# Warmie_Helper_Board.net
KiCad netlist of a schematic drawn in EAGLE
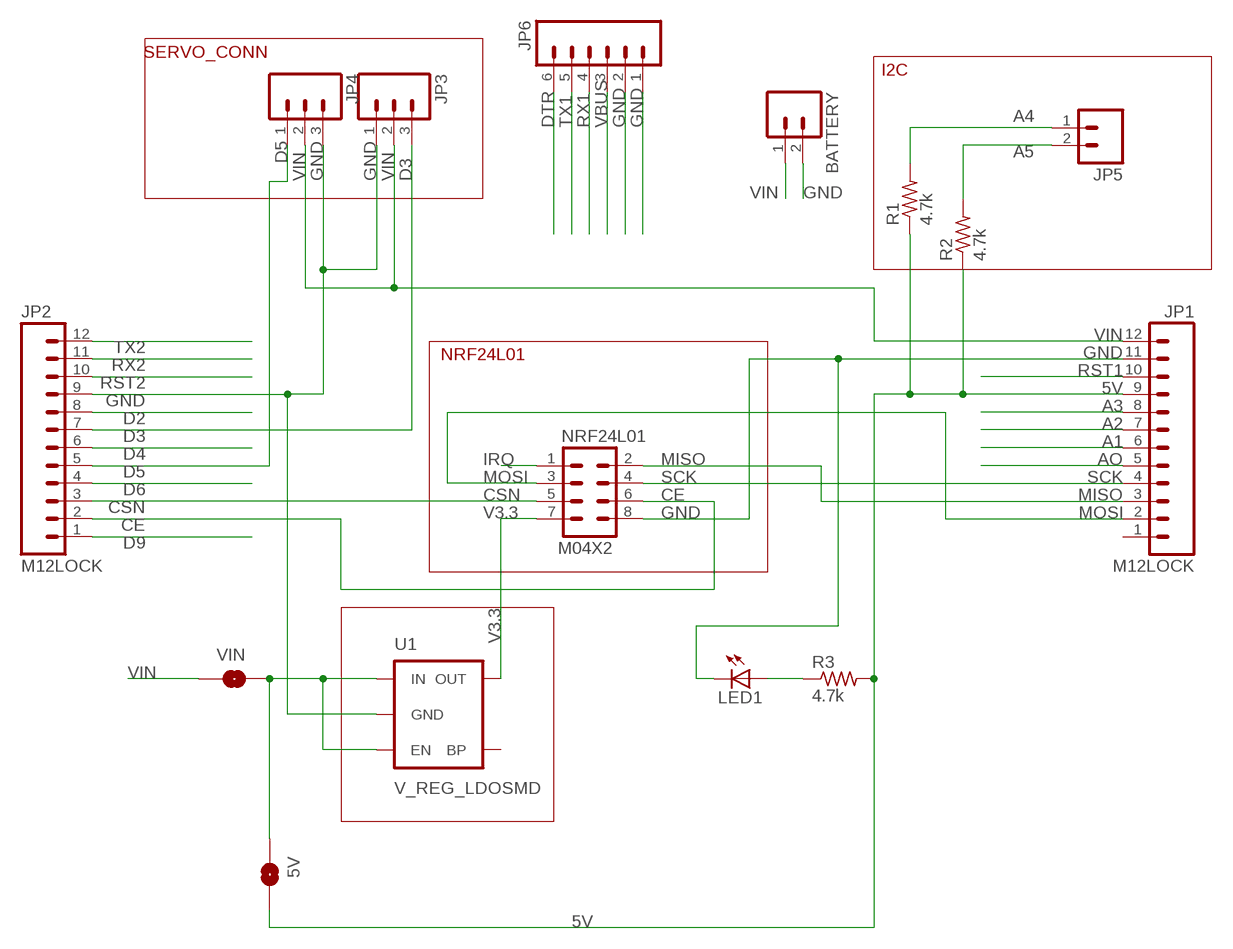
[diagram p0: schematic, sheet 1]

(export (version "E")
  (design (tool "Eeschema 10.0.6"))
  (components
    (comp (ref "5V")
      (value "SOLDERJUMPERNO")
      (footprint "eagle-import:SJ_2S-NO")
      (libsource (lib "eagle-import") (part "SOLDERJUMPERNO"))
    )
    (comp (ref "BATTERY")
      (value "M02LOCK")
      (footprint "eagle-import:1X02_LOCK")
      (libsource (lib "eagle-import") (part "M02LOCK"))
    )
    (comp (ref "JP1")
      (value "M12LOCK")
      (footprint "eagle-import:1X12_LOCK")
      (libsource (lib "eagle-import") (part "M12LOCK"))
    )
    (comp (ref "JP2")
      (value "M12LOCK")
      (footprint "eagle-import:1X12_LOCK")
      (libsource (lib "eagle-import") (part "M12LOCK"))
    )
    (comp (ref "JP3")
      (value "M03LOCK")
      (footprint "eagle-import:1X03_LOCK")
      (libsource (lib "eagle-import") (part "M03LOCK"))
    )
    (comp (ref "JP4")
      (value "M03LOCK")
      (footprint "eagle-import:1X03_LOCK")
      (libsource (lib "eagle-import") (part "M03LOCK"))
    )
    (comp (ref "JP5")
      (value "M02LOCK")
      (footprint "eagle-import:1X02_LOCK")
      (libsource (lib "eagle-import") (part "M02LOCK"))
    )
    (comp (ref "JP6")
      (value "M06LOCK")
      (footprint "eagle-import:1X06_LOCK")
      (libsource (lib "eagle-import") (part "M06LOCK"))
    )
    (comp (ref "LED1")
      (value "LEDSML0603")
      (footprint "eagle-import:SML0603")
      (libsource (lib "eagle-import") (part "LEDSML0603"))
    )
    (comp (ref "NRF24L01")
      (value "M04X2")
      (footprint "eagle-import:2X4")
      (libsource (lib "eagle-import") (part "M04X2"))
    )
    (comp (ref "R1")
      (value "4.7k")
      (footprint "eagle-import:M0805")
      (libsource (lib "eagle-import") (part "R-US_M0805"))
    )
    (comp (ref "R2")
      (value "4.7k")
      (footprint "eagle-import:M0805")
      (libsource (lib "eagle-import") (part "R-US_M0805"))
    )
    (comp (ref "R3")
      (value "4.7k")
      (footprint "eagle-import:M0805")
      (libsource (lib "eagle-import") (part "R-US_M0805"))
    )
    (comp (ref "U1")
      (value "V_REG_LDOSMD")
      (footprint "eagle-import:SOT23-5")
      (libsource (lib "eagle-import") (part "V_REG_LDOSMD"))
    )
    (comp (ref "VIN")
      (value "SOLDERJUMPERNO")
      (footprint "eagle-import:SJ_2S-NO")
      (libsource (lib "eagle-import") (part "SOLDERJUMPERNO"))
    )
  )
  (nets
    (net (code "1") (name "/5V") (class "Default")
      (node (ref "5V") (pin "2") (pinfunction "2_2") (pintype "passive"))
      (node (ref "JP1") (pin "9") (pinfunction "9_9") (pintype "passive"))
      (node (ref "R1") (pin "1") (pinfunction "1_1") (pintype "passive"))
      (node (ref "R2") (pin "1") (pinfunction "1_1") (pintype "passive"))
      (node (ref "R3") (pin "2") (pinfunction "2_2") (pintype "passive"))
    )
    (net (code "2") (name "/A1") (class "Default")
      (node (ref "JP1") (pin "6") (pinfunction "6_6") (pintype "passive"))
    )
    (net (code "3") (name "/A2") (class "Default")
      (node (ref "JP1") (pin "7") (pinfunction "7_7") (pintype "passive"))
    )
    (net (code "4") (name "/A3") (class "Default")
      (node (ref "JP1") (pin "8") (pinfunction "8_8") (pintype "passive"))
    )
    (net (code "5") (name "/A4") (class "Default")
      (node (ref "JP5") (pin "1") (pinfunction "1_1") (pintype "passive"))
      (node (ref "R1") (pin "2") (pinfunction "2_2") (pintype "passive"))
    )
    (net (code "6") (name "/A5") (class "Default")
      (node (ref "JP5") (pin "2") (pinfunction "2_2") (pintype "passive"))
      (node (ref "R2") (pin "2") (pinfunction "2_2") (pintype "passive"))
    )
    (net (code "7") (name "/AO") (class "Default")
      (node (ref "JP1") (pin "5") (pinfunction "5_5") (pintype "passive"))
    )
    (net (code "8") (name "/CE") (class "Default")
      (node (ref "JP2") (pin "2") (pinfunction "2_2") (pintype "passive"))
      (node (ref "NRF24L01") (pin "6") (pinfunction "6_6") (pintype "passive"))
    )
    (net (code "9") (name "/CSN") (class "Default")
      (node (ref "JP2") (pin "3") (pinfunction "3_3") (pintype "passive"))
      (node (ref "NRF24L01") (pin "5") (pinfunction "5_5") (pintype "passive"))
    )
    (net (code "10") (name "/D2") (class "Default")
      (node (ref "JP2") (pin "8") (pinfunction "8_8") (pintype "passive"))
    )
    (net (code "11") (name "/D3") (class "Default")
      (node (ref "JP2") (pin "7") (pinfunction "7_7") (pintype "passive"))
      (node (ref "JP3") (pin "3") (pinfunction "3_3") (pintype "passive"))
    )
    (net (code "12") (name "/D4") (class "Default")
      (node (ref "JP2") (pin "6") (pinfunction "6_6") (pintype "passive"))
    )
    (net (code "13") (name "/D5") (class "Default")
      (node (ref "JP2") (pin "5") (pinfunction "5_5") (pintype "passive"))
      (node (ref "JP4") (pin "1") (pinfunction "1_1") (pintype "passive"))
    )
    (net (code "14") (name "/D6") (class "Default")
      (node (ref "JP2") (pin "4") (pinfunction "4_4") (pintype "passive"))
    )
    (net (code "15") (name "/D9") (class "Default")
      (node (ref "JP2") (pin "1") (pinfunction "1_1") (pintype "passive"))
    )
    (net (code "16") (name "/DTR") (class "Default")
      (node (ref "JP6") (pin "6") (pinfunction "6_6") (pintype "passive"))
    )
    (net (code "17") (name "/GND") (class "Default")
      (node (ref "BATTERY") (pin "2") (pinfunction "2_2") (pintype "passive"))
      (node (ref "JP1") (pin "11") (pinfunction "11_11") (pintype "passive"))
      (node (ref "JP2") (pin "9") (pinfunction "9_9") (pintype "passive"))
      (node (ref "JP3") (pin "1") (pinfunction "1_1") (pintype "passive"))
      (node (ref "JP4") (pin "3") (pinfunction "3_3") (pintype "passive"))
      (node (ref "JP6") (pin "1") (pinfunction "1_1") (pintype "passive"))
      (node (ref "JP6") (pin "2") (pinfunction "2_2") (pintype "passive"))
      (node (ref "LED1") (pin "C") (pinfunction "C_C") (pintype "passive"))
      (node (ref "NRF24L01") (pin "8") (pinfunction "8_8") (pintype "passive"))
      (node (ref "U1") (pin "2") (pinfunction "GND_2") (pintype "input"))
    )
    (net (code "18") (name "/IRQ") (class "Default")
      (node (ref "NRF24L01") (pin "1") (pinfunction "1_1") (pintype "passive"))
    )
    (net (code "19") (name "/MISO") (class "Default")
      (node (ref "JP1") (pin "3") (pinfunction "3_3") (pintype "passive"))
      (node (ref "NRF24L01") (pin "2") (pinfunction "2_2") (pintype "passive"))
    )
    (net (code "20") (name "/MOSI") (class "Default")
      (node (ref "JP1") (pin "2") (pinfunction "2_2") (pintype "passive"))
      (node (ref "NRF24L01") (pin "3") (pinfunction "3_3") (pintype "passive"))
    )
    (net (code "21") (name "/RST1") (class "Default")
      (node (ref "JP1") (pin "10") (pinfunction "10_10") (pintype "passive"))
    )
    (net (code "22") (name "/RST2") (class "Default")
      (node (ref "JP2") (pin "10") (pinfunction "10_10") (pintype "passive"))
    )
    (net (code "23") (name "/RX1") (class "Default")
      (node (ref "JP6") (pin "4") (pinfunction "4_4") (pintype "passive"))
    )
    (net (code "24") (name "/RX2") (class "Default")
      (node (ref "JP2") (pin "11") (pinfunction "11_11") (pintype "passive"))
    )
    (net (code "25") (name "/SCK") (class "Default")
      (node (ref "JP1") (pin "4") (pinfunction "4_4") (pintype "passive"))
      (node (ref "NRF24L01") (pin "4") (pinfunction "4_4") (pintype "passive"))
    )
    (net (code "26") (name "/TX1") (class "Default")
      (node (ref "JP6") (pin "5") (pinfunction "5_5") (pintype "passive"))
    )
    (net (code "27") (name "/TX2") (class "Default")
      (node (ref "JP2") (pin "12") (pinfunction "12_12") (pintype "passive"))
    )
    (net (code "28") (name "/V3.3") (class "Default")
      (node (ref "NRF24L01") (pin "7") (pinfunction "7_7") (pintype "passive"))
      (node (ref "U1") (pin "5") (pinfunction "OUT_5") (pintype "passive"))
    )
    (net (code "29") (name "/VBUS") (class "Default")
      (node (ref "JP6") (pin "3") (pinfunction "3_3") (pintype "passive"))
    )
    (net (code "30") (name "/VIN") (class "Default")
      (node (ref "BATTERY") (pin "1") (pinfunction "1_1") (pintype "passive"))
      (node (ref "JP1") (pin "12") (pinfunction "12_12") (pintype "passive"))
      (node (ref "JP3") (pin "2") (pinfunction "2_2") (pintype "passive"))
      (node (ref "JP4") (pin "2") (pinfunction "2_2") (pintype "passive"))
      (node (ref "VIN") (pin "1") (pinfunction "1_1") (pintype "passive"))
    )
    (net (code "31") (name "Net-(LED1-PadA)") (class "Default")
      (node (ref "LED1") (pin "A") (pinfunction "A_A") (pintype "passive"))
      (node (ref "R3") (pin "1") (pinfunction "1_1") (pintype "passive"))
    )
    (net (code "32") (name "Net-(U1-EN)") (class "Default")
      (node (ref "5V") (pin "1") (pinfunction "1_1") (pintype "passive"))
      (node (ref "U1") (pin "1") (pinfunction "IN_1") (pintype "input"))
      (node (ref "U1") (pin "3") (pinfunction "EN_3") (pintype "input"))
      (node (ref "VIN") (pin "2") (pinfunction "2_2") (pintype "passive"))
    )
    (net (code "33") (name "unconnected-(JP1-Pad1)") (class "Default")
      (node (ref "JP1") (pin "1") (pinfunction "1_1") (pintype "passive"))
    )
    (net (code "34") (name "unconnected-(U1-BP-Pad4)") (class "Default")
      (node (ref "U1") (pin "4") (pinfunction "BP_4") (pintype "input"))
    )
  )
)
